# Single_cell_module.net
KiCad netlist of a schematic drawn in Altium Designer
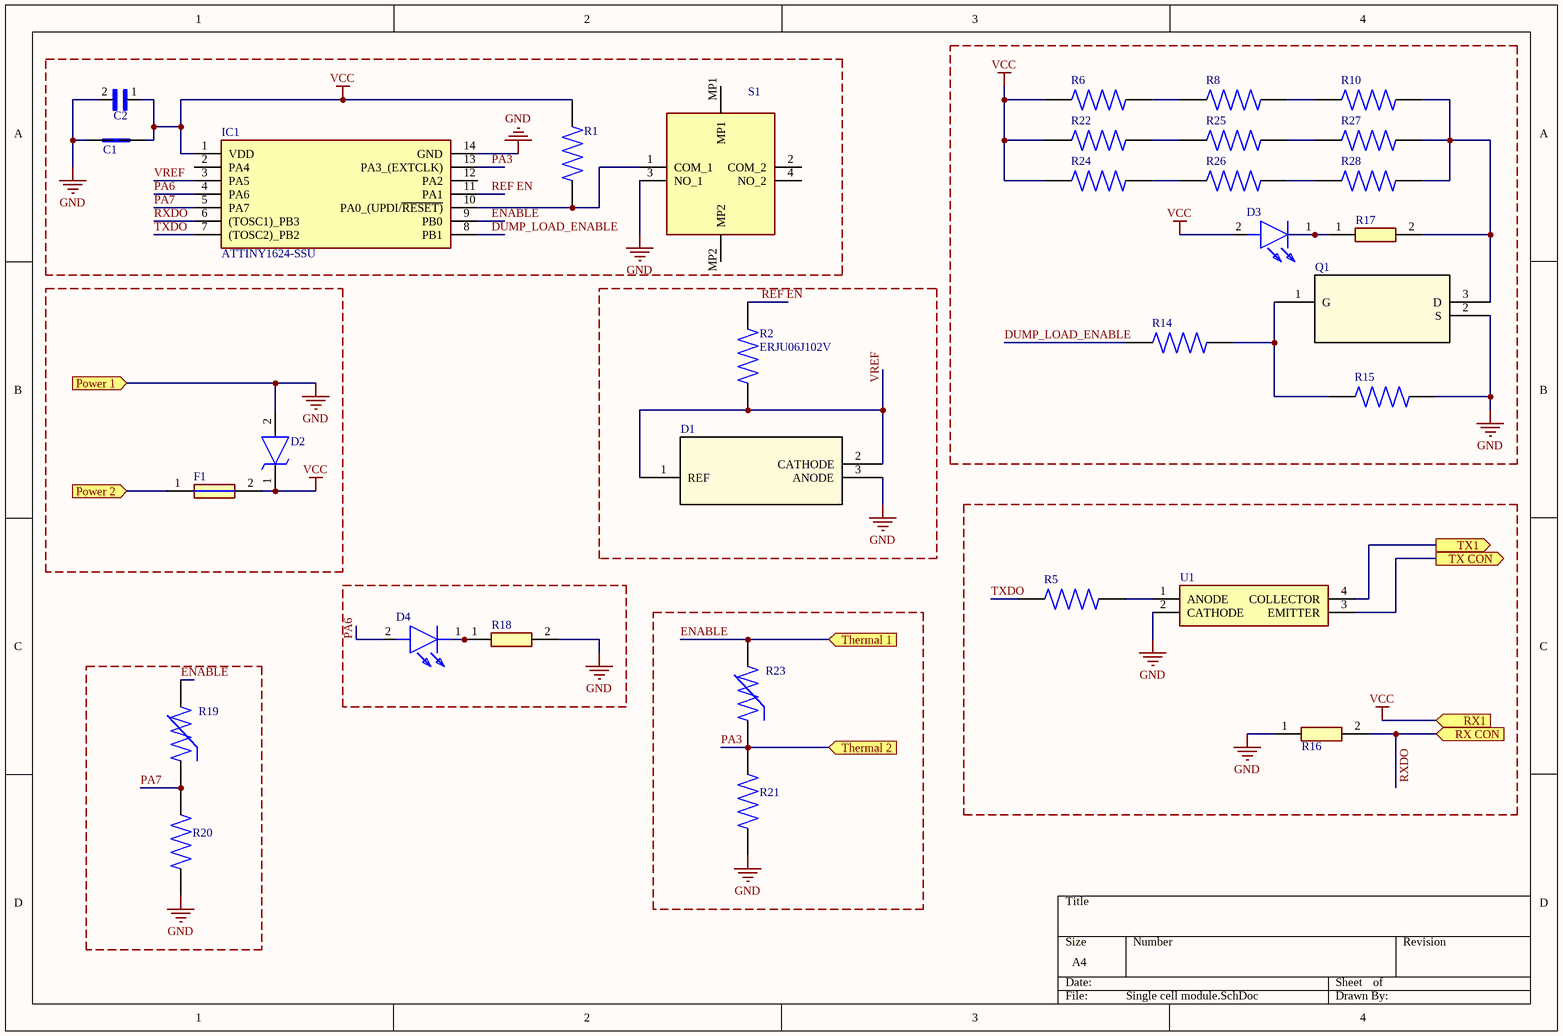
[diagram p0: Single cell module.SchDoc]

(export (version "E")
  (design (tool "Eeschema 10.0.6"))
  (components
    (comp (ref "C1")
      (value "CC0805KRX7R9BB104")
      (footprint "CAPC2012X70")
      (description "0.1ÂµF Â±10% 50V Ceramic Capacitor X7R 0805 _2012 Metric_")
      (fields (field (name "MF") "Yageo"))
      (libsource (lib "CC0805KRX7R9BB104") (part "CC0805KRX7R9BB104"))
    )
    (comp (ref "C2")
      (value "CL21A106KAYNNNE")
      (footprint "CAPC2012X135N")
      (description "10ÂµF Â±10% 25V Ceramic Capacitor X5R 0805 (2012 Metric)")
      (fields (field (name "MF") "Samsung") (field (name "DIGI-KEY_PART_NUMBER") "1276-2891-1-ND"))
      (libsource (lib "CL21A106KAYNNNE") (part "CL21A106KAYNNNE"))
    )
    (comp (ref "D1")
      (value "AZ432ANTR-E1")
      (footprint "SOT-23_DIO")
      (description "No Description Available")
      (libsource (lib "AZ432ANTR-E1") (part "AZ432ANTR-E1"))
    )
    (comp (ref "D2")
      (value "SM6T6V8A")
      (footprint "SamacSys:DIOM5436X265N")
      (description "TVS Diode (Uni-directional)")
      (fields (field (name "MOUSER PART NUMBER") "511-SM6T6V8A"))
      (libsource (lib "*") (part "SM6T6V8A"))
    )
    (comp (ref "D3")
      (value "19-217_GHC-YR1S2_3T")
      (footprint "SamacSys:LEDC1608X50N")
      (description "LED")
      (fields
        (field (name "MANUFACTURER_PART_NUMBER") "19-217/GHC-YR1S2/3T")
        (field (name "MOUSER PART NUMBER") "638-19217GHCYR1S23T")
      )
      (libsource (lib "*") (part "19-217_GHC-YR1S2_3T"))
    )
    (comp (ref "D4")
      (value "19-217_GHC-YR1S2_3T")
      (footprint "SamacSys:LEDC1608X50N")
      (description "LED")
      (fields
        (field (name "MANUFACTURER_PART_NUMBER") "19-217/GHC-YR1S2/3T")
        (field (name "MOUSER PART NUMBER") "638-19217GHCYR1S23T")
      )
      (libsource (lib "*") (part "19-217_GHC-YR1S2_3T"))
    )
    (comp (ref "F1")
      (value "MF-MSMF150-2")
      (footprint "SamacSys:FUSC4632X85N")
      (description "Fuse")
      (fields (field (name "MOUSER PART NUMBER") "652-MF-MSMF150-2"))
      (libsource (lib "*") (part "MF-MSMF150-2"))
    )
    (comp (ref "IC1")
      (value "ATTINY1624-SSU")
      (footprint "SamacSys:SOIC127P600X175-14N")
      (description "Integrated Circuit")
      (fields (field (name "MOUSER PART NUMBER") "556-ATTINY1624-SSU"))
      (libsource (lib "*") (part "ATTINY1624-SSU"))
    )
    (comp (ref "Q1")
      (value "AO3400A")
      (footprint "SOT-23-3L_AOS")
      (description "No Description Available")
      (libsource (lib "AO3400A") (part "AO3400A"))
    )
    (comp (ref "R1")
      (value "ERA6ARW104V")
      (footprint "RES_ERA6ARW104V")
      (libsource (lib "ERA6ARW104V") (part "ERA6ARW104V"))
    )
    (comp (ref "R2")
      (value "ERJU06J102V")
      (footprint "RES_ERJU06J102V")
      (libsource (lib "ERJU06J102V") (part "ERJU06J102V"))
    )
    (comp (ref "R5")
      (value "ERJ6ENF1800V")
      (footprint "RES_ERJ6ENF1800V")
      (libsource (lib "ERJ6ENF1800V") (part "ERJ6ENF1800V"))
    )
    (comp (ref "R6")
      (value "ERA6ARW104V")
      (footprint "RES_ERA6ARW104V")
      (libsource (lib "ERA6ARW104V") (part "ERA6ARW104V"))
    )
    (comp (ref "R8")
      (value "ERA6ARW104V")
      (footprint "RES_ERA6ARW104V")
      (libsource (lib "ERA6ARW104V") (part "ERA6ARW104V"))
    )
    (comp (ref "R10")
      (value "ERA6ARW104V")
      (footprint "RES_ERA6ARW104V")
      (libsource (lib "ERA6ARW104V") (part "ERA6ARW104V"))
    )
    (comp (ref "R14")
      (value "RT1206DRD07510RL")
      (footprint "RESC3116X65N")
      (description "RES SMD 510 OHM 0.5% 1/8W 1206")
      (libsource (lib "RT1206DRD07510RL") (part "RT1206DRD07510RL"))
    )
    (comp (ref "R15")
      (value "ERJP06D1002V")
      (footprint "RES_ERJP06D1002V")
      (libsource (lib "ERJP06D1002V") (part "ERJP06D1002V"))
    )
    (comp (ref "R16")
      (value "0805W8F2201T5E")
      (footprint "SamacSys:RESC2013X65N")
      (description "Resistor")
      (fields (field (name "MOUSER PART NUMBER") "303-0805W8F2201T5E"))
      (libsource (lib "*") (part "0805W8F2201T5E"))
    )
    (comp (ref "R17")
      (value "0805W8F2201T5E")
      (footprint "SamacSys:RESC2013X65N")
      (description "Resistor")
      (fields (field (name "MOUSER PART NUMBER") "303-0805W8F2201T5E"))
      (libsource (lib "*") (part "0805W8F2201T5E"))
    )
    (comp (ref "R18")
      (value "0805W8F2201T5E")
      (footprint "SamacSys:RESC2013X65N")
      (description "Resistor")
      (fields (field (name "MOUSER PART NUMBER") "303-0805W8F2201T5E"))
      (libsource (lib "*") (part "0805W8F2201T5E"))
    )
    (comp (ref "R19")
      (value "NCP18WF104J03RB")
      (footprint "THRMC1608X95N")
      (description "NTC Thermistor 100k 0603 (1608 Metric)")
      (fields (field (name "MF") "Murata Electronics"))
      (libsource (lib "NCP18WF104J03RB") (part "NCP18WF104J03RB"))
    )
    (comp (ref "R20")
      (value "ERJP06D1002V")
      (footprint "RES_ERJP06D1002V")
      (libsource (lib "ERJP06D1002V") (part "ERJP06D1002V"))
    )
    (comp (ref "R21")
      (value "ERJP06D1002V")
      (footprint "RES_ERJP06D1002V")
      (libsource (lib "ERJP06D1002V") (part "ERJP06D1002V"))
    )
    (comp (ref "R22")
      (value "ERA6ARW104V")
      (footprint "RES_ERA6ARW104V")
      (libsource (lib "ERA6ARW104V") (part "ERA6ARW104V"))
    )
    (comp (ref "R23")
      (value "NCP18WF104J03RB")
      (footprint "THRMC1608X95N")
      (description "NTC Thermistor 100k 0603 (1608 Metric)")
      (fields (field (name "MF") "Murata Electronics"))
      (libsource (lib "NCP18WF104J03RB") (part "NCP18WF104J03RB"))
    )
    (comp (ref "R24")
      (value "ERA6ARW104V")
      (footprint "RES_ERA6ARW104V")
      (libsource (lib "ERA6ARW104V") (part "ERA6ARW104V"))
    )
    (comp (ref "R25")
      (value "ERA6ARW104V")
      (footprint "RES_ERA6ARW104V")
      (libsource (lib "ERA6ARW104V") (part "ERA6ARW104V"))
    )
    (comp (ref "R26")
      (value "ERA6ARW104V")
      (footprint "RES_ERA6ARW104V")
      (libsource (lib "ERA6ARW104V") (part "ERA6ARW104V"))
    )
    (comp (ref "R27")
      (value "ERA6ARW104V")
      (footprint "RES_ERA6ARW104V")
      (libsource (lib "ERA6ARW104V") (part "ERA6ARW104V"))
    )
    (comp (ref "R28")
      (value "ERA6ARW104V")
      (footprint "RES_ERA6ARW104V")
      (libsource (lib "ERA6ARW104V") (part "ERA6ARW104V"))
    )
    (comp (ref "S1")
      (value "TS21-34-035-BK-160-SMT-TR")
      (footprint "SamacSys:TS2134035BK160SMTTR")
      (description "Switch")
      (fields (field (name "MOUSER PART NUMBER") "179-134035BK160SMTTR"))
      (libsource (lib "*") (part "TS21-34-035-BK-160-SMT-TR"))
    )
    (comp (ref "U1")
      (value "EL3H7_B__TA_-G")
      (footprint "SamacSys:SOIC127P700X200-4N")
      (description "Integrated Circuit")
      (fields
        (field (name "MANUFACTURER_PART_NUMBER") "EL3H7(B)(TA)-G")
        (field (name "MOUSER PART NUMBER") "638-EL3H7BTAG")
      )
      (libsource (lib "*") (part "EL3H7_B__TA_-G"))
    )
  )
  (nets
    (net (code "1") (name "/DUMP_LOAD_ENABLE") (class "Default")
      (node (ref "IC1") (pin "8") (pinfunction "PB1_8") (pintype "passive"))
      (node (ref "R14") (pin "1") (pinfunction "1_1") (pintype "passive"))
    )
    (net (code "2") (name "/ENABLE") (class "Default")
      (node (ref "IC1") (pin "9") (pinfunction "PB0_9") (pintype "passive"))
      (node (ref "R19") (pin "2") (pinfunction "2_2") (pintype "passive"))
      (node (ref "R23") (pin "2") (pinfunction "2_2") (pintype "passive"))
    )
    (net (code "3") (name "/PA3") (class "Default")
      (node (ref "IC1") (pin "13") (pinfunction "PA3_(EXTCLK)_13") (pintype "passive"))
      (node (ref "R21") (pin "2") (pinfunction "2_2") (pintype "passive"))
      (node (ref "R23") (pin "1") (pinfunction "1_1") (pintype "passive"))
    )
    (net (code "4") (name "/PA6") (class "Default")
      (node (ref "D4") (pin "2") (pinfunction "A_2") (pintype "passive"))
      (node (ref "IC1") (pin "4") (pinfunction "PA6_4") (pintype "passive"))
    )
    (net (code "5") (name "/PA7") (class "Default")
      (node (ref "IC1") (pin "5") (pinfunction "PA7_5") (pintype "passive"))
      (node (ref "R19") (pin "1") (pinfunction "1_1") (pintype "passive"))
      (node (ref "R20") (pin "2") (pinfunction "2_2") (pintype "passive"))
    )
    (net (code "6") (name "/Power 2") (class "Default")
      (node (ref "F1") (pin "1") (pinfunction "1_1") (pintype "passive"))
    )
    (net (code "7") (name "/REF EN") (class "Default")
      (node (ref "IC1") (pin "11") (pinfunction "PA1_11") (pintype "passive"))
      (node (ref "R2") (pin "2") (pinfunction "2_2") (pintype "passive"))
    )
    (net (code "8") (name "/RXDO") (class "Default")
      (node (ref "IC1") (pin "6") (pinfunction "(TOSC1)_PB3_6") (pintype "passive"))
      (node (ref "R16") (pin "2") (pinfunction "2_2") (pintype "passive"))
    )
    (net (code "9") (name "/TX CON") (class "Default")
      (node (ref "U1") (pin "3") (pinfunction "EMITTER_3") (pintype "passive"))
    )
    (net (code "10") (name "/TX1") (class "Default")
      (node (ref "U1") (pin "4") (pinfunction "COLLECTOR_4") (pintype "passive"))
    )
    (net (code "11") (name "/TXDO") (class "Default")
      (node (ref "IC1") (pin "7") (pinfunction "(TOSC2)_PB2_7") (pintype "passive"))
      (node (ref "R5") (pin "1") (pinfunction "1_1") (pintype "passive"))
    )
    (net (code "12") (name "/VREF") (class "Default")
      (node (ref "D1") (pin "1") (pinfunction "REF_1") (pintype "passive"))
      (node (ref "D1") (pin "2") (pinfunction "CATHODE_2") (pintype "passive"))
      (node (ref "IC1") (pin "3") (pinfunction "PA5_3") (pintype "passive"))
      (node (ref "R2") (pin "1") (pinfunction "1_1") (pintype "passive"))
    )
    (net (code "13") (name "GND") (class "Default")
      (node (ref "C1") (pin "1") (pinfunction "1_1") (pintype "passive"))
      (node (ref "C2") (pin "2") (pinfunction "2_2") (pintype "passive"))
      (node (ref "D1") (pin "3") (pinfunction "ANODE_3") (pintype "passive"))
      (node (ref "D2") (pin "2") (pinfunction "A_2") (pintype "passive"))
      (node (ref "IC1") (pin "14") (pinfunction "GND_14") (pintype "passive"))
      (node (ref "Q1") (pin "2") (pinfunction "S_2") (pintype "passive"))
      (node (ref "R15") (pin "2") (pinfunction "2_2") (pintype "passive"))
      (node (ref "R16") (pin "1") (pinfunction "1_1") (pintype "passive"))
      (node (ref "R18") (pin "2") (pinfunction "2_2") (pintype "passive"))
      (node (ref "R20") (pin "1") (pinfunction "1_1") (pintype "passive"))
      (node (ref "R21") (pin "1") (pinfunction "1_1") (pintype "passive"))
      (node (ref "S1") (pin "3") (pinfunction "NO_1_3") (pintype "passive"))
      (node (ref "U1") (pin "2") (pinfunction "CATHODE_2") (pintype "passive"))
    )
    (net (code "14") (name "Net-(D3-K)") (class "Default")
      (node (ref "D3") (pin "1") (pinfunction "K_1") (pintype "passive"))
      (node (ref "R17") (pin "1") (pinfunction "1_1") (pintype "passive"))
    )
    (net (code "15") (name "Net-(D4-K)") (class "Default")
      (node (ref "D4") (pin "1") (pinfunction "K_1") (pintype "passive"))
      (node (ref "R18") (pin "1") (pinfunction "1_1") (pintype "passive"))
    )
    (net (code "16") (name "Net-(IC1-PA0_(UPDI{slash}~{RESET)})") (class "Default")
      (node (ref "IC1") (pin "10") (pinfunction "PA0_(UPDI/~{RESET)}_10") (pintype "passive"))
      (node (ref "R1") (pin "1") (pinfunction "1_1") (pintype "passive"))
      (node (ref "S1") (pin "1") (pinfunction "COM_1_1") (pintype "passive"))
    )
    (net (code "17") (name "Net-(Q1-D)") (class "Default")
      (node (ref "Q1") (pin "3") (pinfunction "D_3") (pintype "passive"))
      (node (ref "R10") (pin "2") (pinfunction "2_2") (pintype "passive"))
      (node (ref "R17") (pin "2") (pinfunction "2_2") (pintype "passive"))
      (node (ref "R27") (pin "2") (pinfunction "2_2") (pintype "passive"))
      (node (ref "R28") (pin "2") (pinfunction "2_2") (pintype "passive"))
    )
    (net (code "18") (name "Net-(Q1-G)") (class "Default")
      (node (ref "Q1") (pin "1") (pinfunction "G_1") (pintype "passive"))
      (node (ref "R14") (pin "2") (pinfunction "2_2") (pintype "passive"))
      (node (ref "R15") (pin "1") (pinfunction "1_1") (pintype "passive"))
    )
    (net (code "19") (name "Net-(R6-Pad2)") (class "Default")
      (node (ref "R6") (pin "2") (pinfunction "2_2") (pintype "passive"))
      (node (ref "R8") (pin "1") (pinfunction "1_1") (pintype "passive"))
    )
    (net (code "20") (name "Net-(R10-Pad1)") (class "Default")
      (node (ref "R10") (pin "1") (pinfunction "1_1") (pintype "passive"))
      (node (ref "R8") (pin "2") (pinfunction "2_2") (pintype "passive"))
    )
    (net (code "21") (name "Net-(R22-Pad2)") (class "Default")
      (node (ref "R22") (pin "2") (pinfunction "2_2") (pintype "passive"))
      (node (ref "R25") (pin "1") (pinfunction "1_1") (pintype "passive"))
    )
    (net (code "22") (name "Net-(R24-Pad2)") (class "Default")
      (node (ref "R24") (pin "2") (pinfunction "2_2") (pintype "passive"))
      (node (ref "R26") (pin "1") (pinfunction "1_1") (pintype "passive"))
    )
    (net (code "23") (name "Net-(R25-Pad2)") (class "Default")
      (node (ref "R25") (pin "2") (pinfunction "2_2") (pintype "passive"))
      (node (ref "R27") (pin "1") (pinfunction "1_1") (pintype "passive"))
    )
    (net (code "24") (name "Net-(R26-Pad2)") (class "Default")
      (node (ref "R26") (pin "2") (pinfunction "2_2") (pintype "passive"))
      (node (ref "R28") (pin "1") (pinfunction "1_1") (pintype "passive"))
    )
    (net (code "25") (name "Net-(U1-ANODE)") (class "Default")
      (node (ref "R5") (pin "2") (pinfunction "2_2") (pintype "passive"))
      (node (ref "U1") (pin "1") (pinfunction "ANODE_1") (pintype "passive"))
    )
    (net (code "26") (name "VCC") (class "Default")
      (node (ref "C1") (pin "2") (pinfunction "2_2") (pintype "passive"))
      (node (ref "C2") (pin "1") (pinfunction "1_1") (pintype "passive"))
      (node (ref "D2") (pin "1") (pinfunction "K_1") (pintype "passive"))
      (node (ref "D3") (pin "2") (pinfunction "A_2") (pintype "passive"))
      (node (ref "F1") (pin "2") (pinfunction "2_2") (pintype "passive"))
      (node (ref "IC1") (pin "1") (pinfunction "VDD_1") (pintype "passive"))
      (node (ref "R1") (pin "2") (pinfunction "2_2") (pintype "passive"))
      (node (ref "R22") (pin "1") (pinfunction "1_1") (pintype "passive"))
      (node (ref "R24") (pin "1") (pinfunction "1_1") (pintype "passive"))
      (node (ref "R6") (pin "1") (pinfunction "1_1") (pintype "passive"))
    )
    (net (code "27") (name "unconnected-(IC1-PA2-Pad12)") (class "Default")
      (node (ref "IC1") (pin "12") (pinfunction "PA2_12") (pintype "passive"))
    )
    (net (code "28") (name "unconnected-(IC1-PA4-Pad2)") (class "Default")
      (node (ref "IC1") (pin "2") (pinfunction "PA4_2") (pintype "passive"))
    )
    (net (code "29") (name "unconnected-(S1-COM_2-Pad2)") (class "Default")
      (node (ref "S1") (pin "2") (pinfunction "COM_2_2") (pintype "passive"))
    )
    (net (code "30") (name "unconnected-(S1-NO_2-Pad4)") (class "Default")
      (node (ref "S1") (pin "4") (pinfunction "NO_2_4") (pintype "passive"))
    )
    (net (code "31") (name "unconnected-(S1-PadMP1)") (class "Default")
      (node (ref "S1") (pin "MP1") (pinfunction "MP1_MP1") (pintype "passive"))
    )
    (net (code "32") (name "unconnected-(S1-PadMP2)") (class "Default")
      (node (ref "S1") (pin "MP2") (pinfunction "MP2_MP2") (pintype "passive"))
    )
  )
)
